# SCH_Arduino-Train-v_2_2026-09-03.net
KiCad netlist of a schematic drawn in EasyEDA
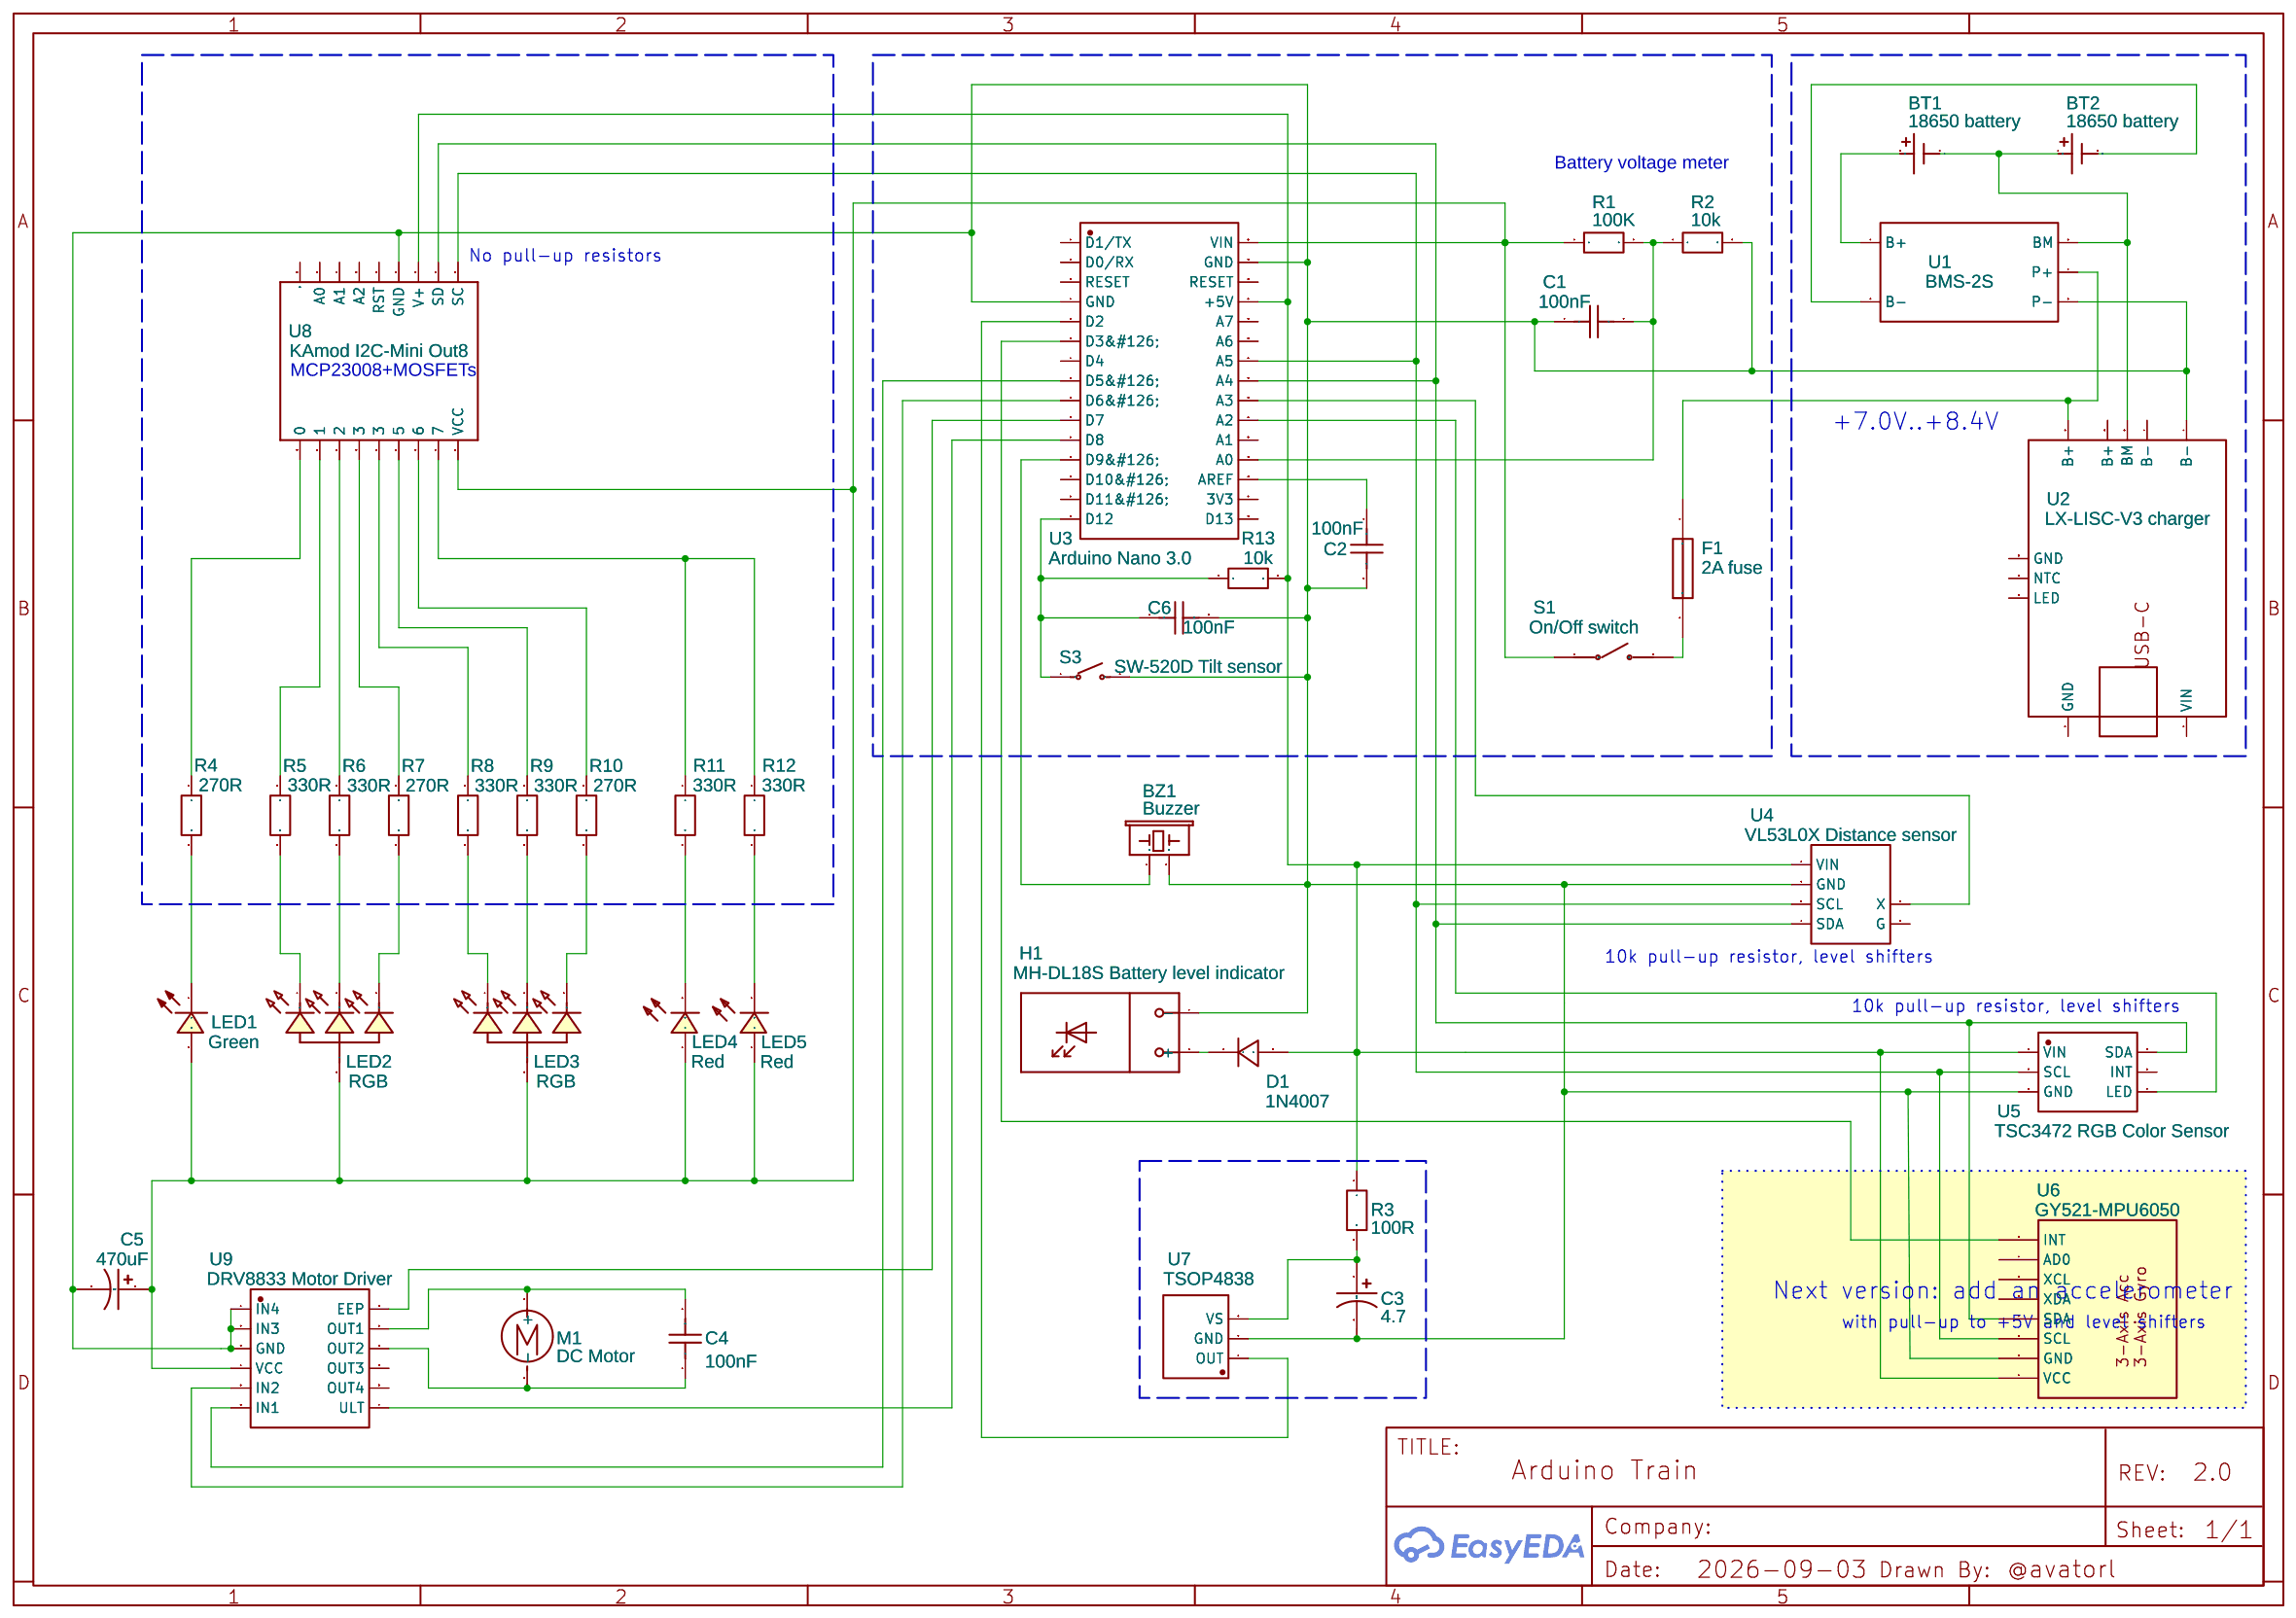
[diagram p0: schematic sheet]

(export (version "E")
  (design (tool "Eeschema 10.0.6"))
  (components
    (comp (ref "BT1") (value "18650 battery") (libsource (lib "") (part "BAT-18650")))
    (comp (ref "BT2") (value "18650 battery") (libsource (lib "") (part "BAT-18650")))
    (comp (ref "BZ1") (value "Buzzer") (libsource (lib "") (part "BUZZER")))
    (comp (ref "C1") (value "100nF") (libsource (lib "") (part "C_0603_US_2")))
    (comp (ref "C2") (value "100nF") (libsource (lib "") (part "C_0603_US_1")))
    (comp (ref "C3")
      (value "4.7")
      (fields (field (name "Manufacturer Part") "B32672P5105J000") (field (name "Manufacturer") "TDK"))
      (libsource (lib "") (part "C_Tan_SMD_A_US_1"))
    )
    (comp (ref "C4") (value "100nF") (libsource (lib "") (part "C_0603_US_3")))
    (comp (ref "C5")
      (value "470uF")
      (fields (field (name "Manufacturer Part") "B32672P5105J000") (field (name "Manufacturer") "TDK"))
      (libsource (lib "") (part "C_Tan_SMD_A_US"))
    )
    (comp (ref "C6") (value "100nF") (libsource (lib "") (part "C_0603_US")))
    (comp (ref "D1") (value "1N4007") (libsource (lib "") (part "1N4007")))
    (comp (ref "F1") (value "2A fuse") (libsource (lib "") (part "FUSE BLADE_PCB_MOUNT COPY")))
    (comp (ref "H1") (value "MH-DL18S Battery level indicator") (libsource (lib "") (part "MH-DL18S")))
    (comp (ref "LED1")
      (value "Green")
      (fields (field (name "Manufacturer Part") "LED三色(Red,Yellow,Green)"))
      (libsource (lib "") (part "LED (GREEN)"))
    )
    (comp (ref "LED2")
      (value "RGB")
      (fields (field (name "Manufacturer Part") "3528反贴RGB 6028反贴RGB 缺口蓝色"))
      (libsource (lib "") (part "3528RGB 6028RGB"))
    )
    (comp (ref "LED3")
      (value "RGB")
      (fields (field (name "Manufacturer Part") "3528反贴RGB 6028反贴RGB 缺口蓝色"))
      (libsource (lib "") (part "3528RGB 6028RGB"))
    )
    (comp (ref "LED4")
      (value "Red")
      (fields (field (name "Manufacturer Part") "LED-3mm红"))
      (libsource (lib "") (part "LED"))
    )
    (comp (ref "LED5")
      (value "Red")
      (fields (field (name "Manufacturer Part") "LED-3mm红"))
      (libsource (lib "") (part "LED"))
    )
    (comp (ref "M1") (value "DC Motor") (libsource (lib "") (part "Motor_DC")))
    (comp (ref "R1") (value "100K") (libsource (lib "") (part "R_0603_EU_1")))
    (comp (ref "R2") (value "10k") (libsource (lib "") (part "R_0603_EU_1")))
    (comp (ref "R3") (value "100R") (libsource (lib "") (part "R_0603_EU")))
    (comp (ref "R4") (value "270R") (libsource (lib "") (part "R_0603_EU")))
    (comp (ref "R5") (value "330R") (libsource (lib "") (part "R_0603_EU")))
    (comp (ref "R6") (value "330R") (libsource (lib "") (part "R_0603_EU")))
    (comp (ref "R7") (value "270R") (libsource (lib "") (part "R_0603_EU")))
    (comp (ref "R8") (value "330R") (libsource (lib "") (part "R_0603_EU")))
    (comp (ref "R9") (value "330R") (libsource (lib "") (part "R_0603_EU")))
    (comp (ref "R10") (value "270R") (libsource (lib "") (part "R_0603_EU")))
    (comp (ref "R11") (value "330R") (libsource (lib "") (part "R_0603_EU")))
    (comp (ref "R12") (value "330R") (libsource (lib "") (part "R_0603_EU")))
    (comp (ref "R13") (value "10k") (libsource (lib "") (part "R_0603_EU_1")))
    (comp (ref "S1")
      (value "On/Off switch")
      (fields (field (name "Manufacturer Part") "BUTTON"))
      (libsource (lib "") (part "BUTTON"))
    )
    (comp (ref "S3")
      (value "SW-520D Tilt sensor")
      (fields
        (field (name "Manufacturer Part") "SW-520DS-AB12G")
        (field (name "Manufacturer") "XKB Connection(中国星坤)")
      )
      (libsource (lib "") (part "SW-520DS-AB12G"))
    )
    (comp (ref "U1")
      (value "BMS-2S")
      (fields (field (name "Manufacturer Part") "HX-2S-D01"))
      (libsource (lib "") (part "2S 3A-10A Lithium Li-ion 18650 Battery BMS Protection PCB Board 7.4v/8.4V"))
    )
    (comp (ref "U2") (value "LX-LISC-V3 charger") (libsource (lib "") (part "LX-LISC-V1")))
    (comp (ref "U3")
      (value "Arduino Nano 3.0")
      (fields (field (name "Manufacturer Part") "ARDUINO_NANO"))
      (libsource (lib "") (part "ARDUINO_NANO"))
    )
    (comp (ref "U4")
      (value "VL53L0X Distance sensor")
      (fields (field (name "Manufacturer Part") "IDC Box 2X4 2.54MM") (field (name "Manufacturer") "BOOMELE"))
      (libsource (lib "") (part "GYUL53L0X_UPDATED final"))
    )
    (comp (ref "U5")
      (value "TSC3472 RGB Color Sensor")
      (fields (field (name "Manufacturer Part") "TCS34725FN") (field (name "Manufacturer") "ams(艾迈斯半导体)"))
      (libsource (lib "") (part "TCS34725FN"))
    )
    (comp (ref "U6") (value "GY521-MPU6050") (libsource (lib "") (part "GY521-MPU6050")))
    (comp (ref "U7")
      (value "TSOP4838")
      (fields (field (name "Manufacturer") "VISHAY(威世)"))
      (libsource (lib "") (part "TSOP4838"))
    )
    (comp (ref "U8") (value "KAmod I2C-Mini Out8") (libsource (lib "") (part "MCP23008P")))
    (comp (ref "U9")
      (value "DRV8833 Motor Driver")
      (fields (field (name "Manufacturer Part") "DRV8833"))
      (libsource (lib "") (part "DRV8833 - Motor Driver"))
    )
  )
  (nets
    (net (code "1") (name "Net-(BT1-N)") (class "Default")
      (node (ref "BT1") (pin "2") (pinfunction "N_2") (pintype "bidirectional"))
      (node (ref "BT2") (pin "1") (pinfunction "P_1") (pintype "bidirectional"))
      (node (ref "U1") (pin "5") (pinfunction "BM_5") (pintype "unspecified"))
      (node (ref "U2") (pin "5") (pinfunction "BM_5") (pintype "unspecified"))
    )
    (net (code "2") (name "Net-(BT1-P)") (class "Default")
      (node (ref "BT1") (pin "1") (pinfunction "P_1") (pintype "bidirectional"))
      (node (ref "U1") (pin "1") (pinfunction "B+_1") (pintype "unspecified"))
    )
    (net (code "3") (name "Net-(BT2-N)") (class "Default")
      (node (ref "BT2") (pin "2") (pinfunction "N_2") (pintype "bidirectional"))
      (node (ref "U1") (pin "2") (pinfunction "B-_2") (pintype "unspecified"))
    )
    (net (code "4") (name "Net-(D1-A)") (class "Default")
      (node (ref "D1") (pin "2") (pinfunction "A_2") (pintype "unspecified"))
      (node (ref "R13") (pin "2") (pinfunction "2_2") (pintype "unspecified"))
      (node (ref "R3") (pin "1") (pinfunction "1_1") (pintype "unspecified"))
      (node (ref "U3") (pin "27") (pinfunction "+5V_27") (pintype "unspecified"))
      (node (ref "U4") (pin "1") (pinfunction "VIN_1") (pintype "unspecified"))
      (node (ref "U5") (pin "1") (pinfunction "VIN_1") (pintype "unspecified"))
      (node (ref "U6") (pin "1") (pinfunction "VCC_1") (pintype "passive"))
      (node (ref "U8") (pin "3") (pinfunction "V+_3") (pintype "input"))
    )
    (net (code "5") (name "Net-(D1-K)") (class "Default")
      (node (ref "D1") (pin "1") (pinfunction "K_1") (pintype "unspecified"))
      (node (ref "H1") (pin "3") (pinfunction "+_3") (pintype "unspecified"))
    )
    (net (code "6") (name "Net-(F1-Pad2)") (class "Default")
      (node (ref "F1") (pin "2") (pinfunction "2_2") (pintype "unspecified"))
      (node (ref "S1") (pin "2") (pinfunction "2_2") (pintype "unspecified"))
    )
    (net (code "7") (name "Net-(H1--)") (class "Default")
      (node (ref "BZ1") (pin "2") (pinfunction "2_2") (pintype "unspecified"))
      (node (ref "C1") (pin "1") (pinfunction "1_1") (pintype "unspecified"))
      (node (ref "C2") (pin "2") (pinfunction "2_2") (pintype "unspecified"))
      (node (ref "C3") (pin "2") (pinfunction "2_2") (pintype "unspecified"))
      (node (ref "C5") (pin "2") (pinfunction "2_2") (pintype "unspecified"))
      (node (ref "C6") (pin "2") (pinfunction "2_2") (pintype "unspecified"))
      (node (ref "H1") (pin "4") (pinfunction "-_4") (pintype "unspecified"))
      (node (ref "R2") (pin "2") (pinfunction "2_2") (pintype "unspecified"))
      (node (ref "S3") (pin "2") (pinfunction "2_2") (pintype "unspecified"))
      (node (ref "U1") (pin "3") (pinfunction "P-_3") (pintype "unspecified"))
      (node (ref "U2") (pin "4") (pinfunction "B-_4") (pintype "unspecified"))
      (node (ref "U3") (pin "29") (pinfunction "GND_29") (pintype "unspecified"))
      (node (ref "U3") (pin "4") (pinfunction "GND_4") (pintype "unspecified"))
      (node (ref "U4") (pin "3") (pinfunction "GND_3") (pintype "unspecified"))
      (node (ref "U5") (pin "3") (pinfunction "GND_3") (pintype "unspecified"))
      (node (ref "U6") (pin "2") (pinfunction "GND_2") (pintype "passive"))
      (node (ref "U7") (pin "2") (pinfunction "GND_2") (pintype "unspecified"))
      (node (ref "U8") (pin "4") (pinfunction "GND_4") (pintype "input"))
      (node (ref "U9") (pin "1") (pinfunction "IN4_1") (pintype "unspecified"))
      (node (ref "U9") (pin "2") (pinfunction "IN3_2") (pintype "unspecified"))
      (node (ref "U9") (pin "3") (pinfunction "GND_3") (pintype "unspecified"))
    )
    (net (code "8") (name "Net-(LED1-Pad1)") (class "Default")
      (node (ref "LED1") (pin "1") (pinfunction "1_1") (pintype "unspecified"))
      (node (ref "R4") (pin "2") (pinfunction "2_2") (pintype "unspecified"))
    )
    (net (code "9") (name "Net-(LED2-A)") (class "Default")
      (node (ref "C5") (pin "1") (pinfunction "1_1") (pintype "unspecified"))
      (node (ref "LED1") (pin "2") (pinfunction "2_2") (pintype "unspecified"))
      (node (ref "LED2") (pin "3") (pinfunction "A_3") (pintype "unspecified"))
      (node (ref "LED3") (pin "3") (pinfunction "A_3") (pintype "unspecified"))
      (node (ref "LED4") (pin "1") (pinfunction "1_1") (pintype "unspecified"))
      (node (ref "LED5") (pin "1") (pinfunction "1_1") (pintype "unspecified"))
      (node (ref "R1") (pin "1") (pinfunction "1_1") (pintype "unspecified"))
      (node (ref "S1") (pin "1") (pinfunction "1_1") (pintype "unspecified"))
      (node (ref "U3") (pin "30") (pinfunction "VIN_30") (pintype "unspecified"))
      (node (ref "U8") (pin "18") (pinfunction "VCC_18") (pintype "passive"))
      (node (ref "U9") (pin "4") (pinfunction "VCC_4") (pintype "unspecified"))
    )
    (net (code "10") (name "Net-(LED2-B)") (class "Default")
      (node (ref "LED2") (pin "2") (pinfunction "B_2") (pintype "unspecified"))
      (node (ref "R7") (pin "2") (pinfunction "2_2") (pintype "unspecified"))
    )
    (net (code "11") (name "Net-(LED2-G)") (class "Default")
      (node (ref "LED2") (pin "1") (pinfunction "G_1") (pintype "unspecified"))
      (node (ref "R6") (pin "2") (pinfunction "2_2") (pintype "unspecified"))
    )
    (net (code "12") (name "Net-(LED2-R)") (class "Default")
      (node (ref "LED2") (pin "4") (pinfunction "R_4") (pintype "unspecified"))
      (node (ref "R5") (pin "2") (pinfunction "2_2") (pintype "unspecified"))
    )
    (net (code "13") (name "Net-(LED3-B)") (class "Default")
      (node (ref "LED3") (pin "2") (pinfunction "B_2") (pintype "unspecified"))
      (node (ref "R10") (pin "2") (pinfunction "2_2") (pintype "unspecified"))
    )
    (net (code "14") (name "Net-(LED3-G)") (class "Default")
      (node (ref "LED3") (pin "1") (pinfunction "G_1") (pintype "unspecified"))
      (node (ref "R9") (pin "2") (pinfunction "2_2") (pintype "unspecified"))
    )
    (net (code "15") (name "Net-(LED3-R)") (class "Default")
      (node (ref "LED3") (pin "4") (pinfunction "R_4") (pintype "unspecified"))
      (node (ref "R8") (pin "2") (pinfunction "2_2") (pintype "unspecified"))
    )
    (net (code "16") (name "Net-(LED4-Pad2)") (class "Default")
      (node (ref "LED4") (pin "2") (pinfunction "2_2") (pintype "unspecified"))
      (node (ref "R11") (pin "2") (pinfunction "2_2") (pintype "unspecified"))
    )
    (net (code "17") (name "Net-(LED5-Pad2)") (class "Default")
      (node (ref "LED5") (pin "2") (pinfunction "2_2") (pintype "unspecified"))
      (node (ref "R12") (pin "2") (pinfunction "2_2") (pintype "unspecified"))
    )
    (net (code "18") (name "Net-(M1-+)") (class "Default")
      (node (ref "C4") (pin "2") (pinfunction "2_2") (pintype "unspecified"))
      (node (ref "M1") (pin "1") (pinfunction "+_1") (pintype "unspecified"))
      (node (ref "U9") (pin "11") (pinfunction "OUT1_11") (pintype "unspecified"))
    )
    (net (code "19") (name "Net-(M1--)") (class "Default")
      (node (ref "C4") (pin "1") (pinfunction "1_1") (pintype "unspecified"))
      (node (ref "M1") (pin "2") (pinfunction "-_2") (pintype "unspecified"))
      (node (ref "U9") (pin "10") (pinfunction "OUT2_10") (pintype "unspecified"))
    )
    (net (code "20") (name "Net-(R7-Pad1)") (class "Default")
      (node (ref "R7") (pin "1") (pinfunction "1_1") (pintype "unspecified"))
      (node (ref "U8") (pin "13") (pinfunction "3_13") (pintype "unspecified"))
    )
    (net (code "21") (name "Net-(R8-Pad1)") (class "Default")
      (node (ref "R8") (pin "1") (pinfunction "1_1") (pintype "unspecified"))
      (node (ref "U8") (pin "14") (pinfunction "3_14") (pintype "unspecified"))
    )
    (net (code "22") (name "Net-(U1-P+)") (class "Default")
      (node (ref "F1") (pin "1") (pinfunction "1_1") (pintype "unspecified"))
      (node (ref "U1") (pin "4") (pinfunction "P+_4") (pintype "unspecified"))
      (node (ref "U2") (pin "3") (pinfunction "B+_3") (pintype "unspecified"))
    )
    (net (code "23") (name "Net-(U3-A0)") (class "Default")
      (node (ref "C1") (pin "2") (pinfunction "2_2") (pintype "unspecified"))
      (node (ref "R1") (pin "2") (pinfunction "2_2") (pintype "unspecified"))
      (node (ref "R2") (pin "1") (pinfunction "1_1") (pintype "unspecified"))
      (node (ref "U3") (pin "19") (pinfunction "A0_19") (pintype "unspecified"))
    )
    (net (code "24") (name "Net-(U3-A2)") (class "Default")
      (node (ref "U3") (pin "21") (pinfunction "A2_21") (pintype "unspecified"))
      (node (ref "U5") (pin "4") (pinfunction "LED_4") (pintype "unspecified"))
    )
    (net (code "25") (name "Net-(U3-A3)") (class "Default")
      (node (ref "U3") (pin "22") (pinfunction "A3_22") (pintype "unspecified"))
      (node (ref "U4") (pin "6") (pinfunction "X_6") (pintype "unspecified"))
    )
    (net (code "26") (name "Net-(U3-A4)") (class "Default")
      (node (ref "U3") (pin "23") (pinfunction "A4_23") (pintype "unspecified"))
      (node (ref "U4") (pin "7") (pinfunction "SDA_7") (pintype "unspecified"))
      (node (ref "U5") (pin "6") (pinfunction "SDA_6") (pintype "unspecified"))
      (node (ref "U6") (pin "4") (pinfunction "SDA_4") (pintype "bidirectional"))
      (node (ref "U8") (pin "2") (pinfunction "SD_2") (pintype "unspecified"))
    )
    (net (code "27") (name "Net-(U3-A5)") (class "Default")
      (node (ref "U3") (pin "24") (pinfunction "A5_24") (pintype "unspecified"))
      (node (ref "U4") (pin "5") (pinfunction "SCL_5") (pintype "unspecified"))
      (node (ref "U5") (pin "2") (pinfunction "SCL_2") (pintype "unspecified"))
      (node (ref "U6") (pin "3") (pinfunction "SCL_3") (pintype "bidirectional"))
      (node (ref "U8") (pin "1") (pinfunction "SC_1") (pintype "input"))
    )
    (net (code "28") (name "Net-(U3-AREF)") (class "Default")
      (node (ref "C2") (pin "1") (pinfunction "1_1") (pintype "unspecified"))
      (node (ref "U3") (pin "18") (pinfunction "AREF_18") (pintype "unspecified"))
    )
    (net (code "29") (name "Net-(U3-D2)") (class "Default")
      (node (ref "U3") (pin "5") (pinfunction "D2_5") (pintype "unspecified"))
      (node (ref "U7") (pin "1") (pinfunction "OUT_1") (pintype "unspecified"))
    )
    (net (code "30") (name "Net-(U3-D3&#126;)") (class "Default")
      (node (ref "U3") (pin "6") (pinfunction "D3&#126;_6") (pintype "unspecified"))
      (node (ref "U6") (pin "8") (pinfunction "INT_8") (pintype "output"))
    )
    (net (code "31") (name "Net-(U3-D5&#126;)") (class "Default")
      (node (ref "U3") (pin "8") (pinfunction "D5&#126;_8") (pintype "unspecified"))
      (node (ref "U9") (pin "6") (pinfunction "IN1_6") (pintype "unspecified"))
    )
    (net (code "32") (name "Net-(U3-D6&#126;)") (class "Default")
      (node (ref "U3") (pin "9") (pinfunction "D6&#126;_9") (pintype "unspecified"))
      (node (ref "U9") (pin "5") (pinfunction "IN2_5") (pintype "unspecified"))
    )
    (net (code "33") (name "Net-(U3-D7)") (class "Default")
      (node (ref "U3") (pin "10") (pinfunction "D7_10") (pintype "unspecified"))
      (node (ref "U9") (pin "12") (pinfunction "EEP_12") (pintype "unspecified"))
    )
    (net (code "34") (name "Net-(U3-D8)") (class "Default")
      (node (ref "U3") (pin "11") (pinfunction "D8_11") (pintype "unspecified"))
      (node (ref "U9") (pin "7") (pinfunction "ULT_7") (pintype "unspecified"))
    )
    (net (code "35") (name "Net-(U3-D9&#126;)") (class "Default")
      (node (ref "BZ1") (pin "1") (pinfunction "1_1") (pintype "unspecified"))
      (node (ref "U3") (pin "12") (pinfunction "D9&#126;_12") (pintype "unspecified"))
    )
    (net (code "36") (name "Net-(U3-D12)") (class "Default")
      (node (ref "C6") (pin "1") (pinfunction "1_1") (pintype "unspecified"))
      (node (ref "R13") (pin "1") (pinfunction "1_1") (pintype "unspecified"))
      (node (ref "S3") (pin "1") (pinfunction "1_1") (pintype "unspecified"))
      (node (ref "U3") (pin "15") (pinfunction "D12_15") (pintype "unspecified"))
    )
    (net (code "37") (name "Net-(U7-VS)") (class "Default")
      (node (ref "C3") (pin "1") (pinfunction "1_1") (pintype "unspecified"))
      (node (ref "R3") (pin "2") (pinfunction "2_2") (pintype "unspecified"))
      (node (ref "U7") (pin "3") (pinfunction "VS_3") (pintype "unspecified"))
    )
    (net (code "38") (name "Net-(U8-0)") (class "Default")
      (node (ref "R4") (pin "1") (pinfunction "1_1") (pintype "unspecified"))
      (node (ref "U8") (pin "10") (pinfunction "0_10") (pintype "unspecified"))
    )
    (net (code "39") (name "Net-(U8-1)") (class "Default")
      (node (ref "R5") (pin "1") (pinfunction "1_1") (pintype "unspecified"))
      (node (ref "U8") (pin "11") (pinfunction "1_11") (pintype "unspecified"))
    )
    (net (code "40") (name "Net-(U8-2)") (class "Default")
      (node (ref "R6") (pin "1") (pinfunction "1_1") (pintype "unspecified"))
      (node (ref "U8") (pin "12") (pinfunction "2_12") (pintype "unspecified"))
    )
    (net (code "41") (name "Net-(U8-5)") (class "Default")
      (node (ref "R9") (pin "1") (pinfunction "1_1") (pintype "unspecified"))
      (node (ref "U8") (pin "15") (pinfunction "5_15") (pintype "unspecified"))
    )
    (net (code "42") (name "Net-(U8-6)") (class "Default")
      (node (ref "R10") (pin "1") (pinfunction "1_1") (pintype "unspecified"))
      (node (ref "U8") (pin "16") (pinfunction "6_16") (pintype "unspecified"))
    )
    (net (code "43") (name "Net-(U8-7)") (class "Default")
      (node (ref "R11") (pin "1") (pinfunction "1_1") (pintype "unspecified"))
      (node (ref "R12") (pin "1") (pinfunction "1_1") (pintype "unspecified"))
      (node (ref "U8") (pin "17") (pinfunction "7_17") (pintype "unspecified"))
    )
    (net (code "44") (name "unconnected-(U2-B+-Pad6)") (class "Default")
      (node (ref "U2") (pin "6") (pinfunction "B+_6") (pintype "unspecified"))
    )
    (net (code "45") (name "unconnected-(U2-B--Pad7)") (class "Default")
      (node (ref "U2") (pin "7") (pinfunction "B-_7") (pintype "unspecified"))
    )
    (net (code "46") (name "unconnected-(U2-GND-Pad2)") (class "Default")
      (node (ref "U2") (pin "2") (pinfunction "GND_2") (pintype "unspecified"))
    )
    (net (code "47") (name "unconnected-(U2-GND-Pad10)") (class "Default")
      (node (ref "U2") (pin "10") (pinfunction "GND_10") (pintype "unspecified"))
    )
    (net (code "48") (name "unconnected-(U2-LED-Pad8)") (class "Default")
      (node (ref "U2") (pin "8") (pinfunction "LED_8") (pintype "unspecified"))
    )
    (net (code "49") (name "unconnected-(U2-NTC-Pad9)") (class "Default")
      (node (ref "U2") (pin "9") (pinfunction "NTC_9") (pintype "unspecified"))
    )
    (net (code "50") (name "unconnected-(U2-VIN-Pad1)") (class "Default")
      (node (ref "U2") (pin "1") (pinfunction "VIN_1") (pintype "unspecified"))
    )
    (net (code "51") (name "unconnected-(U3-3V3-Pad17)") (class "Default")
      (node (ref "U3") (pin "17") (pinfunction "3V3_17") (pintype "unspecified"))
    )
    (net (code "52") (name "unconnected-(U3-A1-Pad20)") (class "Default")
      (node (ref "U3") (pin "20") (pinfunction "A1_20") (pintype "unspecified"))
    )
    (net (code "53") (name "unconnected-(U3-A6-Pad25)") (class "Default")
      (node (ref "U3") (pin "25") (pinfunction "A6_25") (pintype "unspecified"))
    )
    (net (code "54") (name "unconnected-(U3-A7-Pad26)") (class "Default")
      (node (ref "U3") (pin "26") (pinfunction "A7_26") (pintype "unspecified"))
    )
    (net (code "55") (name "unconnected-(U3-D0{slash}RX-Pad2)") (class "Default")
      (node (ref "U3") (pin "2") (pinfunction "D0/RX_2") (pintype "unspecified"))
    )
    (net (code "56") (name "unconnected-(U3-D1{slash}TX-Pad1)") (class "Default")
      (node (ref "U3") (pin "1") (pinfunction "D1/TX_1") (pintype "unspecified"))
    )
    (net (code "57") (name "unconnected-(U3-D4-Pad7)") (class "Default")
      (node (ref "U3") (pin "7") (pinfunction "D4_7") (pintype "unspecified"))
    )
    (net (code "58") (name "unconnected-(U3-D10&#126;-Pad13)") (class "Default")
      (node (ref "U3") (pin "13") (pinfunction "D10&#126;_13") (pintype "unspecified"))
    )
    (net (code "59") (name "unconnected-(U3-D11&#126;-Pad14)") (class "Default")
      (node (ref "U3") (pin "14") (pinfunction "D11&#126;_14") (pintype "unspecified"))
    )
    (net (code "60") (name "unconnected-(U3-D13-Pad16)") (class "Default")
      (node (ref "U3") (pin "16") (pinfunction "D13_16") (pintype "unspecified"))
    )
    (net (code "61") (name "unconnected-(U3-RESET-Pad3)") (class "Default")
      (node (ref "U3") (pin "3") (pinfunction "RESET_3") (pintype "unspecified"))
    )
    (net (code "62") (name "unconnected-(U3-RESET-Pad28)") (class "Default")
      (node (ref "U3") (pin "28") (pinfunction "RESET_28") (pintype "unspecified"))
    )
    (net (code "63") (name "unconnected-(U4-G-Pad8)") (class "Default")
      (node (ref "U4") (pin "8") (pinfunction "G_8") (pintype "unspecified"))
    )
    (net (code "64") (name "unconnected-(U5-INT-Pad5)") (class "Default")
      (node (ref "U5") (pin "5") (pinfunction "INT_5") (pintype "unspecified"))
    )
    (net (code "65") (name "unconnected-(U6-AD0-Pad7)") (class "Default")
      (node (ref "U6") (pin "7") (pinfunction "AD0_7") (pintype "input"))
    )
    (net (code "66") (name "unconnected-(U6-XCL-Pad6)") (class "Default")
      (node (ref "U6") (pin "6") (pinfunction "XCL_6") (pintype "bidirectional"))
    )
    (net (code "67") (name "unconnected-(U6-XDA-Pad5)") (class "Default")
      (node (ref "U6") (pin "5") (pinfunction "XDA_5") (pintype "bidirectional"))
    )
    (net (code "68") (name "unconnected-(U8-A0-Pad8)") (class "Default")
      (node (ref "U8") (pin "8") (pinfunction "A0_8") (pintype "output"))
    )
    (net (code "69") (name "unconnected-(U8-A1-Pad7)") (class "Default")
      (node (ref "U8") (pin "7") (pinfunction "A1_7") (pintype "unspecified"))
    )
    (net (code "70") (name "unconnected-(U8-A2-Pad6)") (class "Default")
      (node (ref "U8") (pin "6") (pinfunction "A2_6") (pintype "input"))
    )
    (net (code "71") (name "unconnected-(U8-NC-Pad9)") (class "Default")
      (node (ref "U8") (pin "9") (pinfunction "NC_9") (pintype "passive"))
    )
    (net (code "72") (name "unconnected-(U8-RST-Pad5)") (class "Default")
      (node (ref "U8") (pin "5") (pinfunction "RST_5") (pintype "input"))
    )
    (net (code "73") (name "unconnected-(U9-OUT3-Pad9)") (class "Default")
      (node (ref "U9") (pin "9") (pinfunction "OUT3_9") (pintype "unspecified"))
    )
    (net (code "74") (name "unconnected-(U9-OUT4-Pad8)") (class "Default")
      (node (ref "U9") (pin "8") (pinfunction "OUT4_8") (pintype "unspecified"))
    )
  )
)
